# Sheet1.net
KiCad netlist of a schematic drawn in Altium Designer
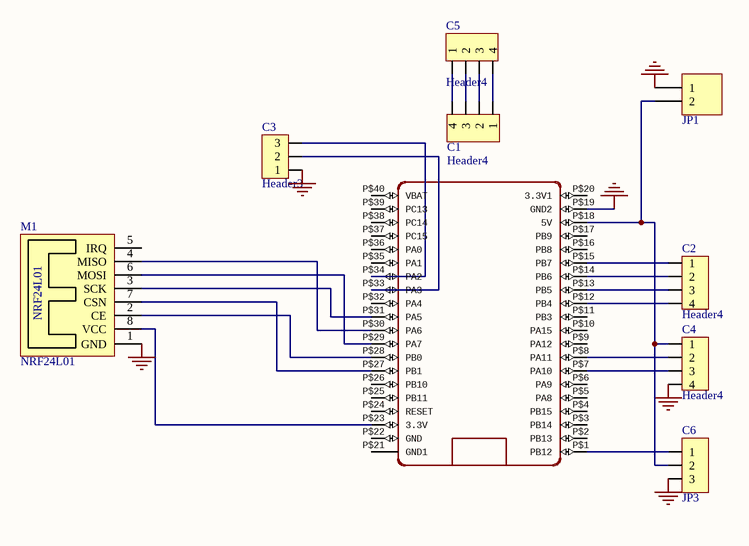
[diagram p0: Sheet1.SchDoc]

(export (version "E")
  (design (tool "Eeschema 10.0.6"))
  (components
    (comp (ref "C1")
      (value "Header4")
      (footprint "Header4")
      (description "Header IDC, 4 x 1 Pin Vertical 2.54mm Pitch (Non-Boxed, Male)")
      (fields
        (field (name "MANUFACTURER") "Würth Elektronik eiSos GmbH")
        (field (name "PARTNO") "613002143121")
        (field (name "CREATED BY") "Karrer Zheng")
      )
      (libsource (lib "My Library") (part "Header4"))
    )
    (comp (ref "C2")
      (value "Header4")
      (footprint "Header4")
      (description "Header IDC, 4 x 1 Pin Vertical 2.54mm Pitch (Non-Boxed, Male)")
      (fields
        (field (name "MANUFACTURER") "Würth Elektronik eiSos GmbH")
        (field (name "PARTNO") "613002143121")
        (field (name "CREATED BY") "Karrer Zheng")
      )
      (libsource (lib "") (part "Header4_1"))
    )
    (comp (ref "C3")
      (value "Header3")
      (footprint "Header3")
      (description "Header IDC, 3 x 1 Pin Vertical 2.54mm Pitch (Non-Boxed, Male)")
      (fields
        (field (name "MANUFACTURER") "Würth Elektronik eiSos GmbH")
        (field (name "PARTNO") "613002143121")
        (field (name "CREATED BY") "Karrer Zheng")
      )
      (libsource (lib "My Library") (part "Header3"))
    )
    (comp (ref "C4")
      (value "Header4")
      (footprint "Header4")
      (description "Header IDC, 4 x 1 Pin Vertical 2.54mm Pitch (Non-Boxed, Male)")
      (fields
        (field (name "MANUFACTURER") "Würth Elektronik eiSos GmbH")
        (field (name "PARTNO") "613002143121")
        (field (name "CREATED BY") "Karrer Zheng")
      )
      (libsource (lib "LIBRARYALT") (part "Header4"))
    )
    (comp (ref "C5")
      (value "Header4")
      (footprint "Header4")
      (description "Header IDC, 4 x 1 Pin Vertical 2.54mm Pitch (Non-Boxed, Male)")
      (fields
        (field (name "MANUFACTURER") "Würth Elektronik eiSos GmbH")
        (field (name "PARTNO") "613002143121")
        (field (name "CREATED BY") "Karrer Zheng")
      )
      (libsource (lib "") (part "Header4_1"))
    )
    (comp (ref "C6")
      (value "JP3")
      (footprint "JP3-D1T")
      (description "WR-PHD 2.54 mm Angled Socket Header")
      (fields
        (field (name "MANUFACTURER") "Würth Elektronik eiSos GmbH")
        (field (name "PARTNO") "613003143121")
        (field (name "CREATED BY") "Karrer Zheng")
      )
      (libsource (lib "LIBRARYALT") (part "JP3"))
    )
    (comp (ref "JP1")
      (value "Header 2_1")
      (footprint "HED2")
      (description "Header, 2-Pin")
      (fields (field (name "MANUFACTURER") "Generic Components"))
      (libsource (lib "echipkool-com-library") (part "Header 2_1"))
    )
    (comp (ref "M1")
      (value "NRF24L01")
      (footprint "NRF24L01")
      (libsource (lib "My Library") (part "NRF24L01"))
    )
    (comp (ref "U")
      (value "BLUE_PILL")
      (footprint "BLUE_PILL")
      (libsource (lib "BluePill") (part "BLUE_PILL"))
    )
  )
  (nets
    (net (code "1") (name "GND") (class "Default")
      (node (ref "C3") (pin "1") (pinfunction "1_1") (pintype "passive"))
      (node (ref "C4") (pin "4") (pinfunction "4_4") (pintype "passive"))
      (node (ref "C6") (pin "3") (pinfunction "3_3") (pintype "passive"))
      (node (ref "JP1") (pin "1") (pinfunction "1_1") (pintype "passive"))
      (node (ref "M1") (pin "1") (pinfunction "GND_1") (pintype "passive"))
      (node (ref "U") (pin "P$19") (pinfunction "GND2_P$19") (pintype "bidirectional"))
    )
    (net (code "2") (name "Net-(C1-Pad1)") (class "Default")
      (node (ref "C1") (pin "1") (pinfunction "1_1") (pintype "passive"))
      (node (ref "C5") (pin "4") (pinfunction "4_4") (pintype "passive"))
    )
    (net (code "3") (name "Net-(C1-Pad2)") (class "Default")
      (node (ref "C1") (pin "2") (pinfunction "2_2") (pintype "passive"))
      (node (ref "C5") (pin "3") (pinfunction "3_3") (pintype "passive"))
    )
    (net (code "4") (name "Net-(C1-Pad3)") (class "Default")
      (node (ref "C1") (pin "3") (pinfunction "3_3") (pintype "passive"))
      (node (ref "C5") (pin "2") (pinfunction "2_2") (pintype "passive"))
    )
    (net (code "5") (name "Net-(C1-Pad4)") (class "Default")
      (node (ref "C1") (pin "4") (pinfunction "4_4") (pintype "passive"))
      (node (ref "C5") (pin "1") (pinfunction "1_1") (pintype "passive"))
    )
    (net (code "6") (name "Net-(M1-CE)") (class "Default")
      (node (ref "M1") (pin "2") (pinfunction "CE_2") (pintype "passive"))
      (node (ref "U") (pin "P$28") (pinfunction "PB0_P$28") (pintype "bidirectional"))
    )
    (net (code "7") (name "Net-(M1-CSN)") (class "Default")
      (node (ref "M1") (pin "7") (pinfunction "CSN_7") (pintype "passive"))
      (node (ref "U") (pin "P$27") (pinfunction "PB1_P$27") (pintype "bidirectional"))
    )
    (net (code "8") (name "Net-(M1-MISO)") (class "Default")
      (node (ref "M1") (pin "4") (pinfunction "MISO_4") (pintype "passive"))
      (node (ref "U") (pin "P$30") (pinfunction "PA6_P$30") (pintype "bidirectional"))
    )
    (net (code "9") (name "Net-(M1-MOSI)") (class "Default")
      (node (ref "M1") (pin "6") (pinfunction "MOSI_6") (pintype "passive"))
      (node (ref "U") (pin "P$29") (pinfunction "PA7_P$29") (pintype "bidirectional"))
    )
    (net (code "10") (name "Net-(M1-SCK)") (class "Default")
      (node (ref "M1") (pin "3") (pinfunction "SCK_3") (pintype "passive"))
      (node (ref "U") (pin "P$31") (pinfunction "PA5_P$31") (pintype "bidirectional"))
    )
    (net (code "11") (name "Net-(M1-VCC)") (class "Default")
      (node (ref "M1") (pin "8") (pinfunction "VCC_8") (pintype "passive"))
      (node (ref "U") (pin "P$23") (pinfunction "3.3V_P$23") (pintype "bidirectional"))
    )
    (net (code "12") (name "Net-(U-5V)") (class "Default")
      (node (ref "C4") (pin "1") (pinfunction "1_1") (pintype "passive"))
      (node (ref "C6") (pin "2") (pinfunction "2_2") (pintype "passive"))
      (node (ref "JP1") (pin "2") (pinfunction "2_2") (pintype "passive"))
      (node (ref "U") (pin "P$18") (pinfunction "5V_P$18") (pintype "bidirectional"))
    )
    (net (code "13") (name "Net-(U-PA2)") (class "Default")
      (node (ref "C3") (pin "3") (pinfunction "3_3") (pintype "passive"))
      (node (ref "U") (pin "P$34") (pinfunction "PA2_P$34") (pintype "bidirectional"))
    )
    (net (code "14") (name "Net-(U-PA3)") (class "Default")
      (node (ref "C3") (pin "2") (pinfunction "2_2") (pintype "passive"))
      (node (ref "U") (pin "P$33") (pinfunction "PA3_P$33") (pintype "bidirectional"))
    )
    (net (code "15") (name "Net-(U-PA10)") (class "Default")
      (node (ref "C4") (pin "3") (pinfunction "3_3") (pintype "passive"))
      (node (ref "U") (pin "P$7") (pinfunction "PA10_P$7") (pintype "bidirectional"))
    )
    (net (code "16") (name "Net-(U-PA11)") (class "Default")
      (node (ref "C4") (pin "2") (pinfunction "2_2") (pintype "passive"))
      (node (ref "U") (pin "P$8") (pinfunction "PA11_P$8") (pintype "bidirectional"))
    )
    (net (code "17") (name "Net-(U-PB4)") (class "Default")
      (node (ref "C2") (pin "4") (pinfunction "4_4") (pintype "passive"))
      (node (ref "U") (pin "P$12") (pinfunction "PB4_P$12") (pintype "bidirectional"))
    )
    (net (code "18") (name "Net-(U-PB5)") (class "Default")
      (node (ref "C2") (pin "3") (pinfunction "3_3") (pintype "passive"))
      (node (ref "U") (pin "P$13") (pinfunction "PB5_P$13") (pintype "bidirectional"))
    )
    (net (code "19") (name "Net-(U-PB6)") (class "Default")
      (node (ref "C2") (pin "2") (pinfunction "2_2") (pintype "passive"))
      (node (ref "U") (pin "P$14") (pinfunction "PB6_P$14") (pintype "bidirectional"))
    )
    (net (code "20") (name "Net-(U-PB7)") (class "Default")
      (node (ref "C2") (pin "1") (pinfunction "1_1") (pintype "passive"))
      (node (ref "U") (pin "P$15") (pinfunction "PB7_P$15") (pintype "bidirectional"))
    )
    (net (code "21") (name "Net-(U-PB12)") (class "Default")
      (node (ref "C6") (pin "1") (pinfunction "1_1") (pintype "passive"))
      (node (ref "U") (pin "P$1") (pinfunction "PB12_P$1") (pintype "bidirectional"))
    )
    (net (code "22") (name "unconnected-(M1-IRQ-Pad5)") (class "Default")
      (node (ref "M1") (pin "5") (pinfunction "IRQ_5") (pintype "passive"))
    )
    (net (code "23") (name "unconnected-(U-3.3V1-PadP$20)") (class "Default")
      (node (ref "U") (pin "P$20") (pinfunction "3.3V1_P$20") (pintype "bidirectional"))
    )
    (net (code "24") (name "unconnected-(U-GND-PadP$22)") (class "Default")
      (node (ref "U") (pin "P$22") (pinfunction "GND_P$22") (pintype "bidirectional"))
    )
    (net (code "25") (name "unconnected-(U-GND1-PadP$21)") (class "Default")
      (node (ref "U") (pin "P$21") (pinfunction "GND1_P$21") (pintype "power_in"))
    )
    (net (code "26") (name "unconnected-(U-PA0-PadP$36)") (class "Default")
      (node (ref "U") (pin "P$36") (pinfunction "PA0_P$36") (pintype "bidirectional"))
    )
    (net (code "27") (name "unconnected-(U-PA1-PadP$35)") (class "Default")
      (node (ref "U") (pin "P$35") (pinfunction "PA1_P$35") (pintype "bidirectional"))
    )
    (net (code "28") (name "unconnected-(U-PA4-PadP$32)") (class "Default")
      (node (ref "U") (pin "P$32") (pinfunction "PA4_P$32") (pintype "bidirectional"))
    )
    (net (code "29") (name "unconnected-(U-PA8-PadP$5)") (class "Default")
      (node (ref "U") (pin "P$5") (pinfunction "PA8_P$5") (pintype "bidirectional"))
    )
    (net (code "30") (name "unconnected-(U-PA9-PadP$6)") (class "Default")
      (node (ref "U") (pin "P$6") (pinfunction "PA9_P$6") (pintype "bidirectional"))
    )
    (net (code "31") (name "unconnected-(U-PA12-PadP$9)") (class "Default")
      (node (ref "U") (pin "P$9") (pinfunction "PA12_P$9") (pintype "bidirectional"))
    )
    (net (code "32") (name "unconnected-(U-PA15-PadP$10)") (class "Default")
      (node (ref "U") (pin "P$10") (pinfunction "PA15_P$10") (pintype "bidirectional"))
    )
    (net (code "33") (name "unconnected-(U-PB3-PadP$11)") (class "Default")
      (node (ref "U") (pin "P$11") (pinfunction "PB3_P$11") (pintype "bidirectional"))
    )
    (net (code "34") (name "unconnected-(U-PB8-PadP$16)") (class "Default")
      (node (ref "U") (pin "P$16") (pinfunction "PB8_P$16") (pintype "bidirectional"))
    )
    (net (code "35") (name "unconnected-(U-PB9-PadP$17)") (class "Default")
      (node (ref "U") (pin "P$17") (pinfunction "PB9_P$17") (pintype "bidirectional"))
    )
    (net (code "36") (name "unconnected-(U-PB10-PadP$26)") (class "Default")
      (node (ref "U") (pin "P$26") (pinfunction "PB10_P$26") (pintype "bidirectional"))
    )
    (net (code "37") (name "unconnected-(U-PB11-PadP$25)") (class "Default")
      (node (ref "U") (pin "P$25") (pinfunction "PB11_P$25") (pintype "bidirectional"))
    )
    (net (code "38") (name "unconnected-(U-PB13-PadP$2)") (class "Default")
      (node (ref "U") (pin "P$2") (pinfunction "PB13_P$2") (pintype "bidirectional"))
    )
    (net (code "39") (name "unconnected-(U-PB14-PadP$3)") (class "Default")
      (node (ref "U") (pin "P$3") (pinfunction "PB14_P$3") (pintype "bidirectional"))
    )
    (net (code "40") (name "unconnected-(U-PB15-PadP$4)") (class "Default")
      (node (ref "U") (pin "P$4") (pinfunction "PB15_P$4") (pintype "bidirectional"))
    )
    (net (code "41") (name "unconnected-(U-PC13-PadP$39)") (class "Default")
      (node (ref "U") (pin "P$39") (pinfunction "PC13_P$39") (pintype "bidirectional"))
    )
    (net (code "42") (name "unconnected-(U-PC14-PadP$38)") (class "Default")
      (node (ref "U") (pin "P$38") (pinfunction "PC14_P$38") (pintype "bidirectional"))
    )
    (net (code "43") (name "unconnected-(U-PC15-PadP$37)") (class "Default")
      (node (ref "U") (pin "P$37") (pinfunction "PC15_P$37") (pintype "bidirectional"))
    )
    (net (code "44") (name "unconnected-(U-RESET-PadP$24)") (class "Default")
      (node (ref "U") (pin "P$24") (pinfunction "RESET_P$24") (pintype "bidirectional"))
    )
    (net (code "45") (name "unconnected-(U-VBAT-PadP$40)") (class "Default")
      (node (ref "U") (pin "P$40") (pinfunction "VBAT_P$40") (pintype "bidirectional"))
    )
  )
)
